# 01_Power_Supply.net
KiCad netlist of a schematic drawn in Altium Designer
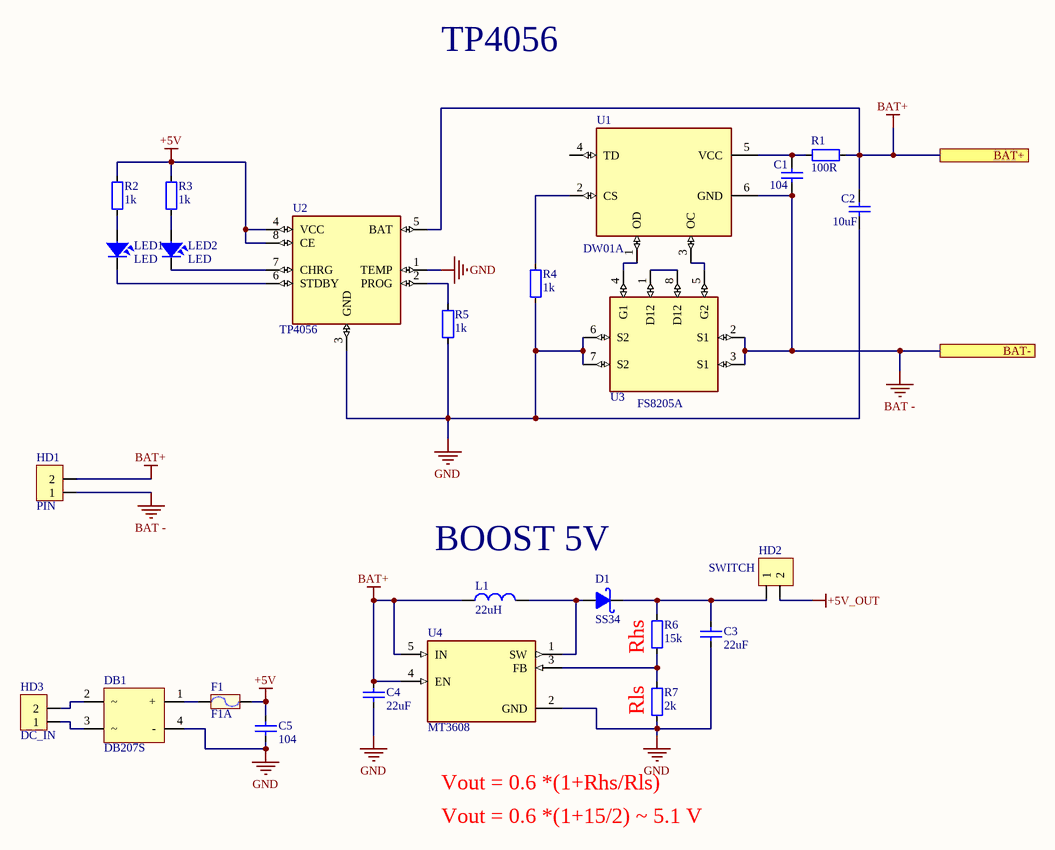
[diagram p0: [01] Power Supply.SchDoc]

(export (version "E")
  (design (tool "Eeschema 10.0.6"))
  (components
    (comp (ref "C1")
      (value "104")
      (footprint "CAP_0805")
      (description "Capacitor")
      (fields (field (name "PUBLISHER") "Altium Limited"))
      (libsource (lib "My Library") (part "CapSMD"))
    )
    (comp (ref "C2")
      (value "10uF")
      (footprint "CAP_0805")
      (description "Capacitor")
      (fields (field (name "PUBLISHER") "Altium Limited"))
      (libsource (lib "My Library") (part "CapSMD"))
    )
    (comp (ref "C3")
      (value "22uF")
      (footprint "CAP_1206")
      (description "Capacitor")
      (fields (field (name "PUBLISHER") "Altium Limited"))
      (libsource (lib "") (part "CapSMD_1"))
    )
    (comp (ref "C4")
      (value "22uF")
      (footprint "CAP_1206")
      (description "Capacitor")
      (fields (field (name "PUBLISHER") "Altium Limited"))
      (libsource (lib "") (part "CapSMD_1"))
    )
    (comp (ref "C5")
      (value "104")
      (footprint "CAP_0805")
      (description "Capacitor")
      (fields (field (name "PUBLISHER") "Altium Limited"))
      (libsource (lib "") (part "CapSMD_1"))
    )
    (comp (ref "D1")
      (value "SS34")
      (footprint "DO-214AA")
      (description "Schottky Rectifiers")
      (libsource (lib "My Library") (part "1N5822"))
    )
    (comp (ref "DB1")
      (value "DB207S")
      (footprint "DB207S")
      (description "Diode Bridge")
      (libsource (lib "My Library") (part "Diode Bridge Flate"))
    )
    (comp (ref "F1")
      (value "F1A")
      (footprint "RES-SMD-1812")
      (description "Fuse")
      (fields (field (name "DESIGNED BY") "VanDungEvn"))
      (libsource (lib "My Library") (part "Fuse"))
    )
    (comp (ref "HD1")
      (value "PIN")
      (footprint "HED2T")
      (description "Header IDC, 2 x 1 Pin Vertical 2.54mm Pitch (Non-Boxed, Male)")
      (fields
        (field (name "MANUFACTURER") "Würth Elektronik eiSos GmbH")
        (field (name "PARTNO") "613002143121")
        (field (name "CREATED BY") "Karrer Zheng")
      )
      (libsource (lib "My Library") (part "Header2"))
    )
    (comp (ref "HD2")
      (value "SWITCH")
      (footprint "HED2T")
      (description "Header IDC, 2 x 1 Pin Vertical 2.54mm Pitch (Non-Boxed, Male)")
      (fields
        (field (name "MANUFACTURER") "Würth Elektronik eiSos GmbH")
        (field (name "PARTNO") "613002143121")
        (field (name "CREATED BY") "Karrer Zheng")
      )
      (libsource (lib "") (part "Header2_1"))
    )
    (comp (ref "HD3")
      (value "DC_IN")
      (footprint "HED2T")
      (description "Header IDC, 2 x 1 Pin Vertical 2.54mm Pitch (Non-Boxed, Male)")
      (fields
        (field (name "MANUFACTURER") "Würth Elektronik eiSos GmbH")
        (field (name "PARTNO") "613002143121")
        (field (name "CREATED BY") "Karrer Zheng")
      )
      (libsource (lib "My Library") (part "Header2"))
    )
    (comp (ref "L1")
      (value "22uH")
      (footprint "CD75-220")
      (description "Inductor 22uH CD75")
      (libsource (lib "My Library") (part "Inductor"))
    )
    (comp (ref "LED1")
      (value "LED")
      (footprint "LED-0805-Green")
      (description "LED Single colour Green and Red")
      (libsource (lib "My Library") (part "LED"))
    )
    (comp (ref "LED2")
      (value "LED")
      (footprint "LED-0805-Red")
      (description "LED Single colour Green and Red")
      (libsource (lib "My Library") (part "LED"))
    )
    (comp (ref "R1")
      (value "100R")
      (footprint "RES-SMD-0805")
      (description "Resistor")
      (fields
        (field (name "MANUFACTURER") "Generic Components")
        (field (name "PUBLISHER") "Altium Hobart Technology Centre")
      )
      (libsource (lib "My Library") (part "Resistor - SMD"))
    )
    (comp (ref "R2")
      (value "1k")
      (footprint "RES-SMD-0805")
      (description "Resistor")
      (fields
        (field (name "MANUFACTURER") "Generic Components")
        (field (name "PUBLISHER") "Altium Hobart Technology Centre")
      )
      (libsource (lib "My Library") (part "Resistor - SMD"))
    )
    (comp (ref "R3")
      (value "1k")
      (footprint "RES-SMD-0805")
      (description "Resistor")
      (fields
        (field (name "MANUFACTURER") "Generic Components")
        (field (name "PUBLISHER") "Altium Hobart Technology Centre")
      )
      (libsource (lib "My Library") (part "Resistor - SMD"))
    )
    (comp (ref "R4")
      (value "1k")
      (footprint "RES-SMD-0805")
      (description "Resistor")
      (fields
        (field (name "MANUFACTURER") "Generic Components")
        (field (name "PUBLISHER") "Altium Hobart Technology Centre")
      )
      (libsource (lib "My Library") (part "Resistor - SMD"))
    )
    (comp (ref "R5")
      (value "1k")
      (footprint "RES-SMD-0805")
      (description "Resistor")
      (fields
        (field (name "MANUFACTURER") "Generic Components")
        (field (name "PUBLISHER") "Altium Hobart Technology Centre")
      )
      (libsource (lib "My Library") (part "Resistor - SMD"))
    )
    (comp (ref "R6")
      (value "15k")
      (footprint "RES-SMD-0805")
      (description "Resistor")
      (fields
        (field (name "MANUFACTURER") "Generic Components")
        (field (name "PUBLISHER") "Altium Hobart Technology Centre")
      )
      (libsource (lib "My Library") (part "Resistor - SMD"))
    )
    (comp (ref "R7")
      (value "2k")
      (footprint "RES-SMD-0805")
      (description "Resistor")
      (fields
        (field (name "MANUFACTURER") "Generic Components")
        (field (name "PUBLISHER") "Altium Hobart Technology Centre")
      )
      (libsource (lib "My Library") (part "Resistor - SMD"))
    )
    (comp (ref "U1")
      (value "DW01A")
      (footprint "SOT23-6")
      (description "One Cell Lithium-ion/Polymer Battery Protection IC")
      (libsource (lib "My Library") (part "DW01A"))
    )
    (comp (ref "U2")
      (value "TP4056")
      (footprint "TP4056")
      (description "Complete single cell Li-Ion battery with a constant current / constant voltage linear charger")
      (libsource (lib "My Library") (part "TP4056"))
    )
    (comp (ref "U3") (value "FS8205A") (footprint "FS8205A") (libsource (lib "My Library") (part "FS8205A")))
    (comp (ref "U4")
      (value "MT3608")
      (footprint "MT3608")
      (description "High Efficiency 1.2MHz 2A Step Up Converter")
      (libsource (lib "My Library") (part "MT3608"))
    )
  )
  (nets
    (net (code "1") (name "+5V") (class "Default")
      (node (ref "C5") (pin "2") (pinfunction "2_2") (pintype "passive"))
      (node (ref "F1") (pin "2") (pinfunction "2_2") (pintype "passive"))
      (node (ref "R2") (pin "2") (pinfunction "2_2") (pintype "passive"))
      (node (ref "R3") (pin "2") (pinfunction "2_2") (pintype "passive"))
      (node (ref "U2") (pin "4") (pinfunction "VCC_4") (pintype "bidirectional"))
      (node (ref "U2") (pin "8") (pinfunction "CE_8") (pintype "bidirectional"))
    )
    (net (code "2") (name "+5V_OUT") (class "Default")
      (node (ref "HD2") (pin "2") (pinfunction "2_2") (pintype "passive"))
    )
    (net (code "3") (name "BAT -") (class "Default")
      (node (ref "C1") (pin "1") (pinfunction "1_1") (pintype "passive"))
      (node (ref "HD1") (pin "1") (pinfunction "1_1") (pintype "passive"))
      (node (ref "U1") (pin "6") (pinfunction "GND_6") (pintype "power_in"))
      (node (ref "U3") (pin "2") (pinfunction "S1_2") (pintype "bidirectional"))
      (node (ref "U3") (pin "3") (pinfunction "S1_3") (pintype "bidirectional"))
    )
    (net (code "4") (name "BAT+") (class "Default")
      (node (ref "C2") (pin "2") (pinfunction "2_2") (pintype "passive"))
      (node (ref "C4") (pin "2") (pinfunction "2_2") (pintype "passive"))
      (node (ref "HD1") (pin "2") (pinfunction "2_2") (pintype "passive"))
      (node (ref "L1") (pin "1") (pinfunction "1_1") (pintype "passive"))
      (node (ref "R1") (pin "1") (pinfunction "1_1") (pintype "passive"))
      (node (ref "U2") (pin "5") (pinfunction "BAT_5") (pintype "bidirectional"))
      (node (ref "U4") (pin "4") (pinfunction "EN_4") (pintype "input"))
      (node (ref "U4") (pin "5") (pinfunction "IN_5") (pintype "input"))
    )
    (net (code "5") (name "GND") (class "Default")
      (node (ref "C2") (pin "1") (pinfunction "1_1") (pintype "passive"))
      (node (ref "C3") (pin "1") (pinfunction "1_1") (pintype "passive"))
      (node (ref "C4") (pin "1") (pinfunction "1_1") (pintype "passive"))
      (node (ref "C5") (pin "1") (pinfunction "1_1") (pintype "passive"))
      (node (ref "DB1") (pin "4") (pinfunction "-_4") (pintype "passive"))
      (node (ref "R4") (pin "1") (pinfunction "1_1") (pintype "passive"))
      (node (ref "R5") (pin "1") (pinfunction "1_1") (pintype "passive"))
      (node (ref "R7") (pin "1") (pinfunction "1_1") (pintype "passive"))
      (node (ref "U2") (pin "1") (pinfunction "TEMP_1") (pintype "bidirectional"))
      (node (ref "U2") (pin "3") (pinfunction "GND_3") (pintype "bidirectional"))
      (node (ref "U3") (pin "6") (pinfunction "S2_6") (pintype "bidirectional"))
      (node (ref "U3") (pin "7") (pinfunction "S2_7") (pintype "bidirectional"))
      (node (ref "U4") (pin "2") (pinfunction "GND_2") (pintype "power_in"))
    )
    (net (code "6") (name "Net-(D1-A)") (class "Default")
      (node (ref "D1") (pin "1") (pinfunction "A_1") (pintype "passive"))
      (node (ref "L1") (pin "2") (pinfunction "2_2") (pintype "passive"))
      (node (ref "U4") (pin "1") (pinfunction "SW_1") (pintype "output"))
    )
    (net (code "7") (name "Net-(D1-K)") (class "Default")
      (node (ref "C3") (pin "2") (pinfunction "2_2") (pintype "passive"))
      (node (ref "D1") (pin "2") (pinfunction "K_2") (pintype "passive"))
      (node (ref "HD2") (pin "1") (pinfunction "1_1") (pintype "passive"))
      (node (ref "R6") (pin "2") (pinfunction "2_2") (pintype "passive"))
    )
    (net (code "8") (name "Net-(DB1-+)") (class "Default")
      (node (ref "DB1") (pin "1") (pinfunction "+_1") (pintype "passive"))
      (node (ref "F1") (pin "1") (pinfunction "1_1") (pintype "passive"))
    )
    (net (code "9") (name "Net-(DB1-~-Pad2)") (class "Default")
      (node (ref "DB1") (pin "2") (pinfunction "~_2") (pintype "passive"))
      (node (ref "HD3") (pin "2") (pinfunction "2_2") (pintype "passive"))
    )
    (net (code "10") (name "Net-(DB1-~-Pad3)") (class "Default")
      (node (ref "DB1") (pin "3") (pinfunction "~_3") (pintype "passive"))
      (node (ref "HD3") (pin "1") (pinfunction "1_1") (pintype "passive"))
    )
    (net (code "11") (name "Net-(LED1-Pad1)") (class "Default")
      (node (ref "LED1") (pin "1") (pinfunction "1_1") (pintype "passive"))
      (node (ref "R2") (pin "1") (pinfunction "1_1") (pintype "passive"))
    )
    (net (code "12") (name "Net-(LED2-Pad1)") (class "Default")
      (node (ref "LED2") (pin "1") (pinfunction "1_1") (pintype "passive"))
      (node (ref "R3") (pin "1") (pinfunction "1_1") (pintype "passive"))
    )
    (net (code "13") (name "Net-(U1-CS)") (class "Default")
      (node (ref "R4") (pin "2") (pinfunction "2_2") (pintype "passive"))
      (node (ref "U1") (pin "2") (pinfunction "CS_2") (pintype "bidirectional"))
    )
    (net (code "14") (name "Net-(U1-OC)") (class "Default")
      (node (ref "U1") (pin "3") (pinfunction "OC_3") (pintype "bidirectional"))
      (node (ref "U3") (pin "5") (pinfunction "G2_5") (pintype "bidirectional"))
    )
    (net (code "15") (name "Net-(U1-OD)") (class "Default")
      (node (ref "U1") (pin "1") (pinfunction "OD_1") (pintype "bidirectional"))
      (node (ref "U3") (pin "4") (pinfunction "G1_4") (pintype "bidirectional"))
    )
    (net (code "16") (name "Net-(U1-VCC)") (class "Default")
      (node (ref "C1") (pin "2") (pinfunction "2_2") (pintype "passive"))
      (node (ref "R1") (pin "2") (pinfunction "2_2") (pintype "passive"))
      (node (ref "U1") (pin "5") (pinfunction "VCC_5") (pintype "power_in"))
    )
    (net (code "17") (name "Net-(U2-CHRG)") (class "Default")
      (node (ref "LED2") (pin "2") (pinfunction "2_2") (pintype "passive"))
      (node (ref "U2") (pin "7") (pinfunction "CHRG_7") (pintype "bidirectional"))
    )
    (net (code "18") (name "Net-(U2-PROG)") (class "Default")
      (node (ref "R5") (pin "2") (pinfunction "2_2") (pintype "passive"))
      (node (ref "U2") (pin "2") (pinfunction "PROG_2") (pintype "bidirectional"))
    )
    (net (code "19") (name "Net-(U2-STDBY)") (class "Default")
      (node (ref "LED1") (pin "2") (pinfunction "2_2") (pintype "passive"))
      (node (ref "U2") (pin "6") (pinfunction "STDBY_6") (pintype "bidirectional"))
    )
    (net (code "20") (name "Net-(U3-D12-Pad1)") (class "Default")
      (node (ref "U3") (pin "1") (pinfunction "D12_1") (pintype "bidirectional"))
      (node (ref "U3") (pin "8") (pinfunction "D12_8") (pintype "bidirectional"))
    )
    (net (code "21") (name "Net-(U4-FB)") (class "Default")
      (node (ref "R6") (pin "1") (pinfunction "1_1") (pintype "passive"))
      (node (ref "R7") (pin "2") (pinfunction "2_2") (pintype "passive"))
      (node (ref "U4") (pin "3") (pinfunction "FB_3") (pintype "input"))
    )
    (net (code "22") (name "unconnected-(U1-TD-Pad4)") (class "Default")
      (node (ref "U1") (pin "4") (pinfunction "TD_4") (pintype "bidirectional"))
    )
  )
)
